# zad1_hw.net
KiCad netlist of a schematic drawn in EAGLE
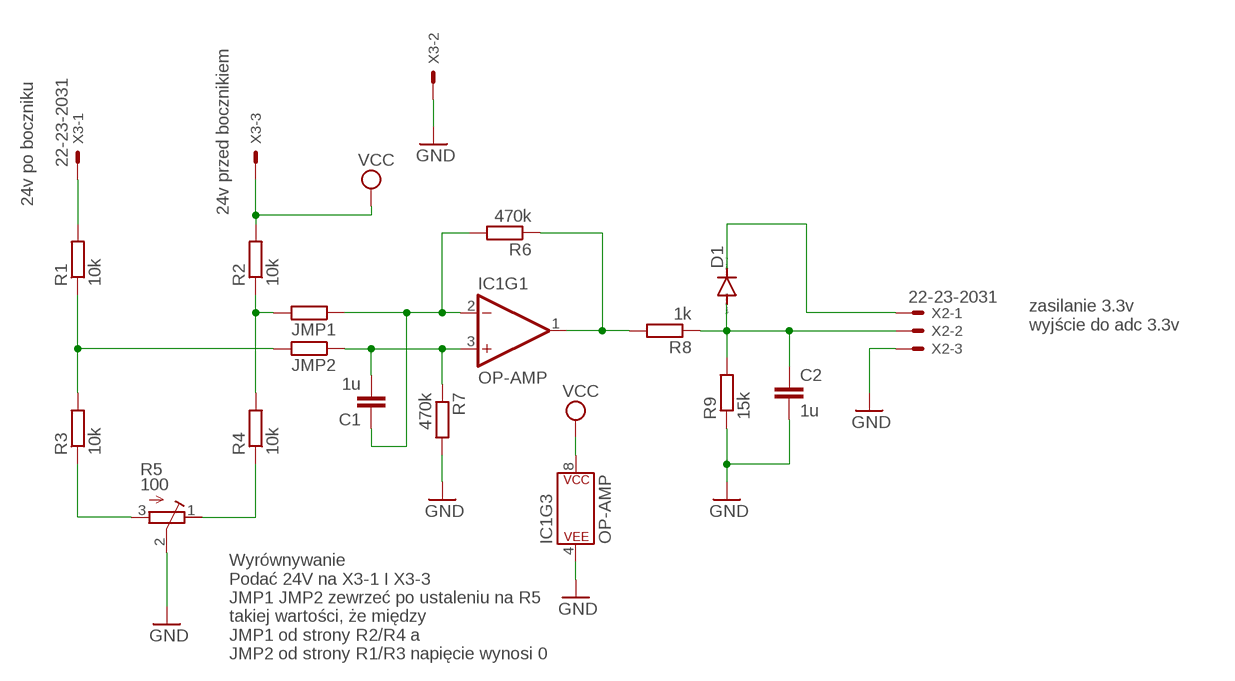
[diagram p0: schematic, sheet 1]

(export (version "E")
  (design (tool "Eeschema 10.0.6"))
  (components
    (comp (ref "C1")
      (value "1u")
      (footprint "eagle-import:C1206")
      (libsource (lib "eagle-import") (part "C-EUC1206"))
    )
    (comp (ref "C2")
      (value "1u")
      (footprint "eagle-import:C1206")
      (libsource (lib "eagle-import") (part "C-EUC1206"))
    )
    (comp (ref "D1")
      (value "DIODE-DO214AC")
      (footprint "eagle-import:DO214AC")
      (libsource (lib "eagle-import") (part "DIODE-DO214AC"))
    )
    (comp (ref "IC1")
      (value "OP-AMP")
      (footprint "eagle-import:SO08")
      (libsource (lib "eagle-import") (part "OPAMP-DUALU"))
    )
    (comp (ref "JMP1")
      (value "0")
      (footprint "eagle-import:R1206")
      (libsource (lib "eagle-import") (part "R-EU_R1206"))
    )
    (comp (ref "JMP2")
      (value "0")
      (footprint "eagle-import:R1206")
      (libsource (lib "eagle-import") (part "R-EU_R1206"))
    )
    (comp (ref "R1")
      (value "10k")
      (footprint "eagle-import:R1206")
      (libsource (lib "eagle-import") (part "R-EU_R1206"))
    )
    (comp (ref "R2")
      (value "10k")
      (footprint "eagle-import:R1206")
      (libsource (lib "eagle-import") (part "R-EU_R1206"))
    )
    (comp (ref "R3")
      (value "10k")
      (footprint "eagle-import:R1206")
      (libsource (lib "eagle-import") (part "R-EU_R1206"))
    )
    (comp (ref "R4")
      (value "10k")
      (footprint "eagle-import:R1206")
      (libsource (lib "eagle-import") (part "R-EU_R1206"))
    )
    (comp (ref "R5")
      (value "100")
      (footprint "eagle-import:RTRIMT93YA")
      (libsource (lib "eagle-import") (part "R-TRIMMT93YA"))
    )
    (comp (ref "R6")
      (value "470k")
      (footprint "eagle-import:R1206")
      (libsource (lib "eagle-import") (part "R-EU_R1206"))
    )
    (comp (ref "R7")
      (value "470k")
      (footprint "eagle-import:R1206")
      (libsource (lib "eagle-import") (part "R-EU_R1206"))
    )
    (comp (ref "R8")
      (value "1k")
      (footprint "eagle-import:R1206")
      (libsource (lib "eagle-import") (part "R-EU_R1206"))
    )
    (comp (ref "R9")
      (value "15k")
      (footprint "eagle-import:R1206")
      (libsource (lib "eagle-import") (part "R-EU_R1206"))
    )
    (comp (ref "X2")
      (value "22-23-2031")
      (footprint "eagle-import:22-23-2031")
      (fields (field (name "MF") "MOLEX"))
      (libsource (lib "eagle-import") (part "22-23-2031"))
    )
    (comp (ref "X3")
      (value "22-23-2031")
      (footprint "eagle-import:22-23-2031")
      (fields (field (name "MF") "MOLEX"))
      (libsource (lib "eagle-import") (part "22-23-2031"))
    )
  )
  (nets
    (net (code "1") (name "GND") (class "Default")
      (node (ref "C2") (pin "2") (pinfunction "2_2") (pintype "passive"))
      (node (ref "IC1") (pin "4") (pinfunction "P$V-_4") (pintype "bidirectional"))
      (node (ref "R5") (pin "2") (pinfunction "S_2") (pintype "passive"))
      (node (ref "R7") (pin "2") (pinfunction "2_2") (pintype "passive"))
      (node (ref "R9") (pin "1") (pinfunction "1_1") (pintype "passive"))
      (node (ref "X2") (pin "3") (pinfunction "S_3") (pintype "passive"))
      (node (ref "X3") (pin "2") (pinfunction "S_2") (pintype "passive"))
    )
    (net (code "2") (name "Net-(IC1A-+IN)") (class "Default")
      (node (ref "C1") (pin "2") (pinfunction "2_2") (pintype "passive"))
      (node (ref "IC1") (pin "3") (pinfunction "+IN_3") (pintype "input"))
      (node (ref "JMP2") (pin "1") (pinfunction "1_1") (pintype "passive"))
      (node (ref "R7") (pin "1") (pinfunction "1_1") (pintype "passive"))
    )
    (net (code "3") (name "Net-(IC1A--IN)") (class "Default")
      (node (ref "C1") (pin "1") (pinfunction "1_1") (pintype "passive"))
      (node (ref "IC1") (pin "2") (pinfunction "-IN_2") (pintype "input"))
      (node (ref "JMP1") (pin "1") (pinfunction "1_1") (pintype "passive"))
      (node (ref "R6") (pin "2") (pinfunction "2_2") (pintype "passive"))
    )
    (net (code "4") (name "Net-(IC1A-OUT)") (class "Default")
      (node (ref "IC1") (pin "1") (pinfunction "OUT_1") (pintype "output"))
      (node (ref "R6") (pin "1") (pinfunction "1_1") (pintype "passive"))
      (node (ref "R8") (pin "2") (pinfunction "2_2") (pintype "passive"))
    )
    (net (code "5") (name "Net-(JMP1-Pad2)") (class "Default")
      (node (ref "JMP1") (pin "2") (pinfunction "2_2") (pintype "passive"))
      (node (ref "R2") (pin "1") (pinfunction "1_1") (pintype "passive"))
      (node (ref "R4") (pin "2") (pinfunction "2_2") (pintype "passive"))
    )
    (net (code "6") (name "Net-(JMP2-Pad2)") (class "Default")
      (node (ref "JMP2") (pin "2") (pinfunction "2_2") (pintype "passive"))
      (node (ref "R1") (pin "1") (pinfunction "1_1") (pintype "passive"))
      (node (ref "R3") (pin "2") (pinfunction "2_2") (pintype "passive"))
    )
    (net (code "7") (name "Net-(R5-A)") (class "Default")
      (node (ref "R3") (pin "1") (pinfunction "1_1") (pintype "passive"))
      (node (ref "R5") (pin "3") (pinfunction "A_3") (pintype "passive"))
    )
    (net (code "8") (name "Net-(R5-E)") (class "Default")
      (node (ref "R4") (pin "1") (pinfunction "1_1") (pintype "passive"))
      (node (ref "R5") (pin "1") (pinfunction "E_1") (pintype "passive"))
    )
    (net (code "9") (name "Net-(X2A-S)") (class "Default")
      (node (ref "D1") (pin "C") (pinfunction "C_C") (pintype "passive"))
      (node (ref "X2") (pin "1") (pinfunction "S_1") (pintype "passive"))
    )
    (net (code "10") (name "Net-(X2B-S)") (class "Default")
      (node (ref "C2") (pin "1") (pinfunction "1_1") (pintype "passive"))
      (node (ref "D1") (pin "A") (pinfunction "A_A") (pintype "passive"))
      (node (ref "R8") (pin "1") (pinfunction "1_1") (pintype "passive"))
      (node (ref "R9") (pin "2") (pinfunction "2_2") (pintype "passive"))
      (node (ref "X2") (pin "2") (pinfunction "S_2") (pintype "passive"))
    )
    (net (code "11") (name "Net-(X3A-S)") (class "Default")
      (node (ref "R1") (pin "2") (pinfunction "2_2") (pintype "passive"))
      (node (ref "X3") (pin "1") (pinfunction "S_1") (pintype "passive"))
    )
    (net (code "12") (name "VCC") (class "Default")
      (node (ref "IC1") (pin "8") (pinfunction "P$V+_8") (pintype "bidirectional"))
      (node (ref "R2") (pin "2") (pinfunction "2_2") (pintype "passive"))
      (node (ref "X3") (pin "3") (pinfunction "S_3") (pintype "passive"))
    )
  )
)
